# E18_Simple_Breakout.net
KiCad netlist of a schematic drawn in EAGLE
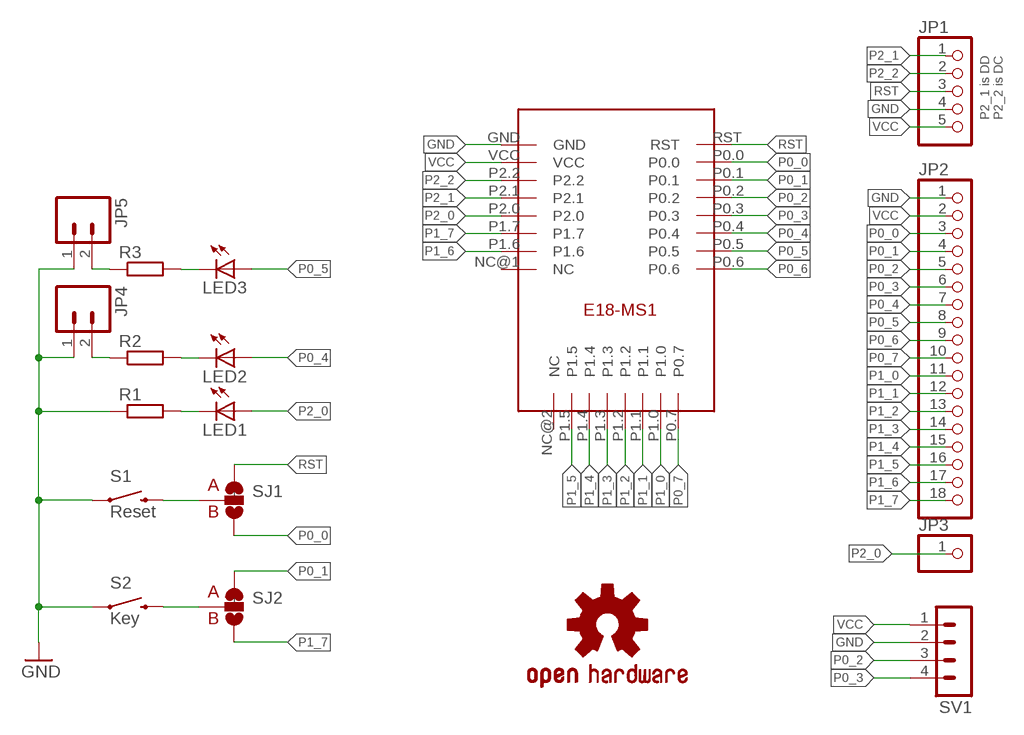
[diagram p0: schematic, sheet 1]

(export (version "E")
  (design (tool "Eeschema 10.0.6"))
  (components
    (comp (ref "JP1")
      (value "PINHD-1X5")
      (footprint "eagle-import:1X05")
      (libsource (lib "eagle-import") (part "PINHD-1X5"))
    )
    (comp (ref "JP2")
      (value "PINHD-1X18")
      (footprint "eagle-import:1X18")
      (libsource (lib "eagle-import") (part "PINHD-1X18"))
    )
    (comp (ref "JP3")
      (value "PINHD-1X1")
      (footprint "eagle-import:1X01")
      (libsource (lib "eagle-import") (part "PINHD-1X1"))
    )
    (comp (ref "JP4")
      (value "HEADER-1X2P1X02_NO_SILK")
      (footprint "eagle-import:1X02_NO_SILK")
      (libsource (lib "eagle-import") (part "HEADER-1X2P1X02_NO_SILK"))
    )
    (comp (ref "JP5")
      (value "HEADER-1X2P1X02_NO_SILK")
      (footprint "eagle-import:1X02_NO_SILK")
      (libsource (lib "eagle-import") (part "HEADER-1X2P1X02_NO_SILK"))
    )
    (comp (ref "LED1")
      (value "LED1206")
      (footprint "eagle-import:LED-1206")
      (libsource (lib "eagle-import") (part "LED1206"))
    )
    (comp (ref "LED2")
      (value "LED1206")
      (footprint "eagle-import:LED-1206")
      (libsource (lib "eagle-import") (part "LED1206"))
    )
    (comp (ref "LED3")
      (value "LED1206")
      (footprint "eagle-import:LED-1206")
      (libsource (lib "eagle-import") (part "LED1206"))
    )
    (comp (ref "LOGO1")
      (value "OSHW-LOGOM")
      (footprint "eagle-import:OSHW-LOGO-M")
      (libsource (lib "eagle-import") (part "OSHW-LOGOM"))
    )
    (comp (ref "R1")
      (value "R-EU_")
      (footprint "eagle-import:1206")
      (libsource (lib "eagle-import") (part "R-EU_"))
    )
    (comp (ref "R2")
      (value "R-EU_")
      (footprint "eagle-import:1206")
      (libsource (lib "eagle-import") (part "R-EU_"))
    )
    (comp (ref "R3")
      (value "R-EU_")
      (footprint "eagle-import:1206")
      (libsource (lib "eagle-import") (part "R-EU_"))
    )
    (comp (ref "S1")
      (value "Reset")
      (footprint "eagle-import:TACTILE-PTH")
      (libsource (lib "eagle-import") (part "SWITCH-MOMENTARY-2PTH"))
    )
    (comp (ref "S2")
      (value "Key")
      (footprint "eagle-import:TACTILE-PTH")
      (libsource (lib "eagle-import") (part "SWITCH-MOMENTARY-2PTH"))
    )
    (comp (ref "SJ1")
      (value "SOLDERJUMPER_2WAYT")
      (footprint "eagle-import:SJ_2")
      (libsource (lib "eagle-import") (part "SOLDERJUMPER_2WAYT"))
    )
    (comp (ref "SJ2")
      (value "SOLDERJUMPER_2WAYT")
      (footprint "eagle-import:SJ_2")
      (libsource (lib "eagle-import") (part "SOLDERJUMPER_2WAYT"))
    )
    (comp (ref "SV1")
      (value "HEADER-1X4P")
      (footprint "eagle-import:MA04-1")
      (libsource (lib "eagle-import") (part "HEADER-1X4P"))
    )
    (comp (ref "U$1")
      (value "E18-MS1PCB")
      (footprint "eagle-import:E18-MS1-PCB")
      (libsource (lib "eagle-import") (part "E18-MS1PCB"))
    )
  )
  (nets
    (net (code "1") (name "GND") (class "Default")
      (node (ref "JP1") (pin "4") (pinfunction "4_4") (pintype "passive"))
      (node (ref "JP2") (pin "1") (pinfunction "1_1") (pintype "passive"))
      (node (ref "JP4") (pin "1") (pinfunction "1_1") (pintype "passive"))
      (node (ref "JP5") (pin "1") (pinfunction "1_1") (pintype "passive"))
      (node (ref "R1") (pin "1") (pinfunction "1_1") (pintype "passive"))
      (node (ref "S1") (pin "1") (pinfunction "1_1") (pintype "passive"))
      (node (ref "S2") (pin "1") (pinfunction "1_1") (pintype "passive"))
      (node (ref "SV1") (pin "2") (pinfunction "2_2") (pintype "passive"))
      (node (ref "U$1") (pin "GND") (pinfunction "GND_GND") (pintype "bidirectional"))
    )
    (net (code "2") (name "Net-(JP4-Pad2)") (class "Default")
      (node (ref "JP4") (pin "2") (pinfunction "2_2") (pintype "passive"))
      (node (ref "R2") (pin "1") (pinfunction "1_1") (pintype "passive"))
    )
    (net (code "3") (name "Net-(JP5-Pad2)") (class "Default")
      (node (ref "JP5") (pin "2") (pinfunction "2_2") (pintype "passive"))
      (node (ref "R3") (pin "1") (pinfunction "1_1") (pintype "passive"))
    )
    (net (code "4") (name "Net-(LED1-PadC)") (class "Default")
      (node (ref "LED1") (pin "C") (pinfunction "C_C") (pintype "passive"))
      (node (ref "R1") (pin "2") (pinfunction "2_2") (pintype "passive"))
    )
    (net (code "5") (name "Net-(LED2-PadC)") (class "Default")
      (node (ref "LED2") (pin "C") (pinfunction "C_C") (pintype "passive"))
      (node (ref "R2") (pin "2") (pinfunction "2_2") (pintype "passive"))
    )
    (net (code "6") (name "Net-(LED3-PadC)") (class "Default")
      (node (ref "LED3") (pin "C") (pinfunction "C_C") (pintype "passive"))
      (node (ref "R3") (pin "2") (pinfunction "2_2") (pintype "passive"))
    )
    (net (code "7") (name "Net-(S1-2)") (class "Default")
      (node (ref "S1") (pin "3") (pinfunction "2_3") (pintype "passive"))
      (node (ref "SJ1") (pin "2") (pinfunction "2_2") (pintype "passive"))
    )
    (net (code "8") (name "Net-(S2-2)") (class "Default")
      (node (ref "S2") (pin "3") (pinfunction "2_3") (pintype "passive"))
      (node (ref "SJ2") (pin "2") (pinfunction "2_2") (pintype "passive"))
    )
    (net (code "9") (name "P0_0") (class "Default")
      (node (ref "JP2") (pin "3") (pinfunction "3_3") (pintype "passive"))
      (node (ref "SJ1") (pin "3") (pinfunction "3_3") (pintype "passive"))
      (node (ref "U$1") (pin "P0.0") (pinfunction "P0.0_P0.0") (pintype "bidirectional"))
    )
    (net (code "10") (name "P0_1") (class "Default")
      (node (ref "JP2") (pin "4") (pinfunction "4_4") (pintype "passive"))
      (node (ref "SJ2") (pin "1") (pinfunction "1_1") (pintype "passive"))
      (node (ref "U$1") (pin "P0.1") (pinfunction "P0.1_P0.1") (pintype "bidirectional"))
    )
    (net (code "11") (name "P0_2") (class "Default")
      (node (ref "JP2") (pin "5") (pinfunction "5_5") (pintype "passive"))
      (node (ref "SV1") (pin "3") (pinfunction "3_3") (pintype "passive"))
      (node (ref "U$1") (pin "P0.2") (pinfunction "P0.2_P0.2") (pintype "bidirectional"))
    )
    (net (code "12") (name "P0_3") (class "Default")
      (node (ref "JP2") (pin "6") (pinfunction "6_6") (pintype "passive"))
      (node (ref "SV1") (pin "4") (pinfunction "4_4") (pintype "passive"))
      (node (ref "U$1") (pin "P0.3") (pinfunction "P0.3_P0.3") (pintype "bidirectional"))
    )
    (net (code "13") (name "P0_4") (class "Default")
      (node (ref "JP2") (pin "7") (pinfunction "7_7") (pintype "passive"))
      (node (ref "LED2") (pin "A") (pinfunction "A_A") (pintype "passive"))
      (node (ref "U$1") (pin "P0.4") (pinfunction "P0.4_P0.4") (pintype "bidirectional"))
    )
    (net (code "14") (name "P0_5") (class "Default")
      (node (ref "JP2") (pin "8") (pinfunction "8_8") (pintype "passive"))
      (node (ref "LED3") (pin "A") (pinfunction "A_A") (pintype "passive"))
      (node (ref "U$1") (pin "P0.5") (pinfunction "P0.5_P0.5") (pintype "bidirectional"))
    )
    (net (code "15") (name "P0_6") (class "Default")
      (node (ref "JP2") (pin "9") (pinfunction "9_9") (pintype "passive"))
      (node (ref "U$1") (pin "P0.6") (pinfunction "P0.6_P0.6") (pintype "bidirectional"))
    )
    (net (code "16") (name "P0_7") (class "Default")
      (node (ref "JP2") (pin "10") (pinfunction "10_10") (pintype "passive"))
      (node (ref "U$1") (pin "P0.7") (pinfunction "P0.7_P0.7") (pintype "bidirectional"))
    )
    (net (code "17") (name "P1_0") (class "Default")
      (node (ref "JP2") (pin "11") (pinfunction "11_11") (pintype "passive"))
      (node (ref "U$1") (pin "P1.0") (pinfunction "P1.0_P1.0") (pintype "bidirectional"))
    )
    (net (code "18") (name "P1_1") (class "Default")
      (node (ref "JP2") (pin "12") (pinfunction "12_12") (pintype "passive"))
      (node (ref "U$1") (pin "P1.1") (pinfunction "P1.1_P1.1") (pintype "bidirectional"))
    )
    (net (code "19") (name "P1_2") (class "Default")
      (node (ref "JP2") (pin "13") (pinfunction "13_13") (pintype "passive"))
      (node (ref "U$1") (pin "P1.2") (pinfunction "P1.2_P1.2") (pintype "bidirectional"))
    )
    (net (code "20") (name "P1_3") (class "Default")
      (node (ref "JP2") (pin "14") (pinfunction "14_14") (pintype "passive"))
      (node (ref "U$1") (pin "P1.3") (pinfunction "P1.3_P1.3") (pintype "bidirectional"))
    )
    (net (code "21") (name "P1_4") (class "Default")
      (node (ref "JP2") (pin "15") (pinfunction "15_15") (pintype "passive"))
      (node (ref "U$1") (pin "P1.4") (pinfunction "P1.4_P1.4") (pintype "bidirectional"))
    )
    (net (code "22") (name "P1_5") (class "Default")
      (node (ref "JP2") (pin "16") (pinfunction "16_16") (pintype "passive"))
      (node (ref "U$1") (pin "P1.5") (pinfunction "P1.5_P1.5") (pintype "bidirectional"))
    )
    (net (code "23") (name "P1_6") (class "Default")
      (node (ref "JP2") (pin "17") (pinfunction "17_17") (pintype "passive"))
      (node (ref "U$1") (pin "P1.6") (pinfunction "P1.6_P1.6") (pintype "bidirectional"))
    )
    (net (code "24") (name "P1_7") (class "Default")
      (node (ref "JP2") (pin "18") (pinfunction "18_18") (pintype "passive"))
      (node (ref "SJ2") (pin "3") (pinfunction "3_3") (pintype "passive"))
      (node (ref "U$1") (pin "P1.7") (pinfunction "P1.7_P1.7") (pintype "bidirectional"))
    )
    (net (code "25") (name "P2_0") (class "Default")
      (node (ref "JP3") (pin "1") (pinfunction "1_1") (pintype "passive"))
      (node (ref "LED1") (pin "A") (pinfunction "A_A") (pintype "passive"))
      (node (ref "U$1") (pin "P2.0") (pinfunction "P2.0_P2.0") (pintype "bidirectional"))
    )
    (net (code "26") (name "P2_1") (class "Default")
      (node (ref "JP1") (pin "1") (pinfunction "1_1") (pintype "passive"))
      (node (ref "U$1") (pin "P2.1") (pinfunction "P2.1_P2.1") (pintype "bidirectional"))
    )
    (net (code "27") (name "P2_2") (class "Default")
      (node (ref "JP1") (pin "2") (pinfunction "2_2") (pintype "passive"))
      (node (ref "U$1") (pin "P2.2") (pinfunction "P2.2_P2.2") (pintype "bidirectional"))
    )
    (net (code "28") (name "RST") (class "Default")
      (node (ref "JP1") (pin "3") (pinfunction "3_3") (pintype "passive"))
      (node (ref "SJ1") (pin "1") (pinfunction "1_1") (pintype "passive"))
      (node (ref "U$1") (pin "RST") (pinfunction "RST_RST") (pintype "bidirectional"))
    )
    (net (code "29") (name "VCC") (class "Default")
      (node (ref "JP1") (pin "5") (pinfunction "5_5") (pintype "passive"))
      (node (ref "JP2") (pin "2") (pinfunction "2_2") (pintype "passive"))
      (node (ref "SV1") (pin "1") (pinfunction "1_1") (pintype "passive"))
      (node (ref "U$1") (pin "VCC") (pinfunction "VCC_VCC") (pintype "bidirectional"))
    )
    (net (code "30") (name "unconnected-(U$1-NC-PadNC@1)") (class "Default")
      (node (ref "U$1") (pin "NC@1") (pinfunction "NC_NC@1") (pintype "bidirectional"))
    )
    (net (code "31") (name "unconnected-(U$1-NC-PadNC@2)") (class "Default")
      (node (ref "U$1") (pin "NC@2") (pinfunction "NC_NC@2") (pintype "bidirectional"))
    )
  )
)
